# Audio_Input_Mic_In.net
KiCad netlist of a schematic drawn in Altium Designer
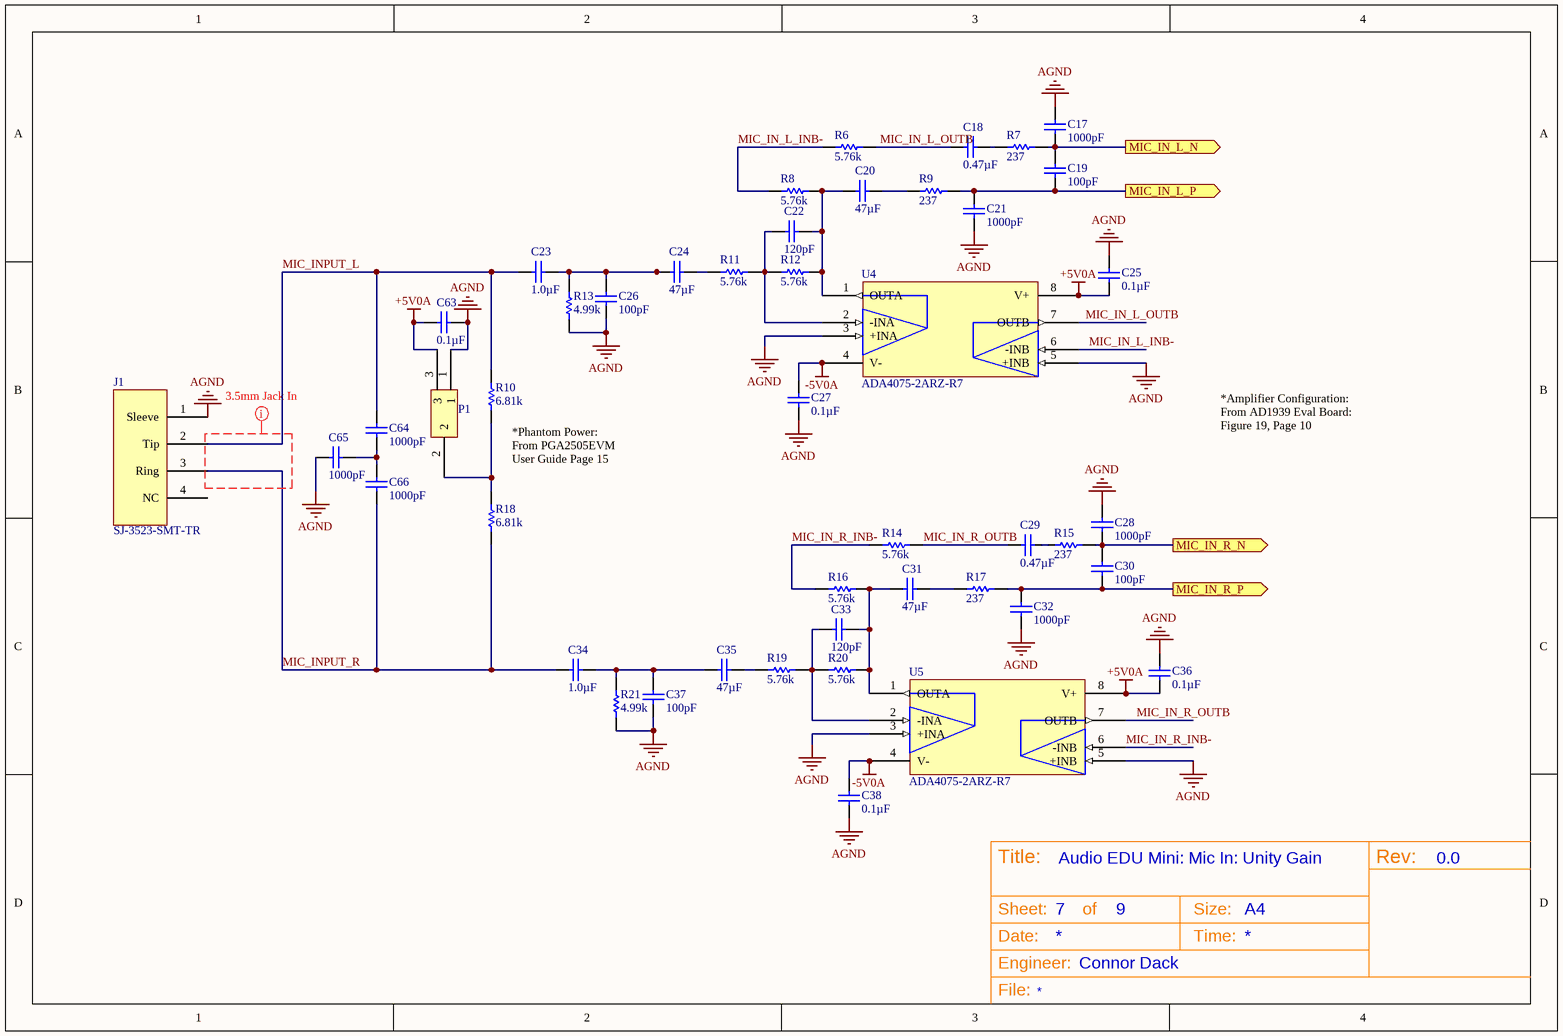
[diagram p0: Audio_Input_Mic_In.SchDoc]

(export (version "E")
  (design (tool "Eeschema 10.0.6"))
  (components
    (comp (ref "C17")
      (value "CL10B102KB8NNNC")
      (footprint "3-0603_L")
      (description "1000pF 50V Ceramic Capacitor X7R 0603 (1608 Metric) 0.063\" L x 0.031\" W (1.60mm x 0.80mm)")
      (fields
        (field (name "MANUFACTURER") "Samsung Electro-Mechanics America, Inc.")
        (field (name "TOLERANCE") "±10%")
        (field (name "CAPACITANCE") "1000pF")
      )
      (libsource (lib "Schematic_Components") (part "CL10B102KB8NNNC"))
    )
    (comp (ref "C18")
      (value "C1608X7R1H474K080AC")
      (footprint "3-0603_L")
      (description "CAP CER 0.47UF 50V 10% X7R 0603")
      (fields
        (field (name "MANUFACTURER") "TDK Corporation")
        (field (name "TOLERANCE") "±10%")
        (field (name "CAPACITANCE") "0.47µF")
      )
      (libsource (lib "Schematic_Components") (part "C1608X7R1H474K080AC"))
    )
    (comp (ref "C19")
      (value "C1608C0G2A101J")
      (footprint "3-0603_L")
      (description "CAP CER 100PF 100V 5% NP0 0603")
      (fields
        (field (name "MANUFACTURER") "TDK Corporation")
        (field (name "TOLERANCE") "±5%")
        (field (name "CAPACITANCE") "100pF")
      )
      (libsource (lib "Schematic_Components") (part "C1608C0G2A101J"))
    )
    (comp (ref "C20")
      (value "GRM32EC81C476KE15L")
      (footprint "C1210X25_L")
      (description "47µF ±10% 16V Ceramic Capacitor X6S 1210 (3225 Metric)")
      (fields
        (field (name "MANUFACTURER") "Murata Electronics North America")
        (field (name "TOLERANCE") "±10%")
        (field (name "CAPACITANCE") "47µF")
      )
      (libsource (lib "Schematic_Components") (part "GRM32EC81C476KE15L"))
    )
    (comp (ref "C21")
      (value "CL10B102KB8NNNC")
      (footprint "3-0603_L")
      (description "1000pF 50V Ceramic Capacitor X7R 0603 (1608 Metric) 0.063\" L x 0.031\" W (1.60mm x 0.80mm)")
      (fields
        (field (name "MANUFACTURER") "Samsung Electro-Mechanics America, Inc.")
        (field (name "TOLERANCE") "±10%")
        (field (name "CAPACITANCE") "1000pF")
      )
      (libsource (lib "Schematic_Components") (part "CL10B102KB8NNNC"))
    )
    (comp (ref "C22")
      (value "CL10C121JB8NCNC")
      (footprint "3-0603_L")
      (description "120pF 50V Ceramic Capacitor C0G, NP0 0603 (1608 Metric) 0.063\" L x 0.031\" W (1.60mm x 0.80mm)")
      (fields
        (field (name "MANUFACTURER") "Samsung Electro-Mechanics America, Inc.")
        (field (name "TOLERANCE") "±5%")
        (field (name "CAPACITANCE") "120pF")
      )
      (libsource (lib "Schematic_Components") (part "CL10C121JB8NCNC"))
    )
    (comp (ref "C23")
      (value "C1608X7R1C105K")
      (footprint "3-0603_L")
      (description "CAP CER 1UF 16V 10% X7R 0603")
      (fields
        (field (name "MANUFACTURER") "TDK Corporation")
        (field (name "TOLERANCE") "±10%")
        (field (name "CAPACITANCE") "1.0µF")
      )
      (libsource (lib "Schematic_Components") (part "C1608X7R1C105K"))
    )
    (comp (ref "C24")
      (value "GRM32EC81C476KE15L")
      (footprint "C1210X25_L")
      (description "47µF ±10% 16V Ceramic Capacitor X6S 1210 (3225 Metric)")
      (fields
        (field (name "MANUFACTURER") "Murata Electronics North America")
        (field (name "TOLERANCE") "±10%")
        (field (name "CAPACITANCE") "47µF")
      )
      (libsource (lib "Schematic_Components") (part "GRM32EC81C476KE15L"))
    )
    (comp (ref "C25")
      (value "C1608X7R1H104K")
      (footprint "3-0603_L")
      (description "CAP CER 0.1UF 50V 10% X7R 0603")
      (fields
        (field (name "MANUFACTURER") "TDK Corporation")
        (field (name "TOLERANCE") "±10%")
        (field (name "CAPACITANCE") "0.1µF")
      )
      (libsource (lib "Schematic_Components") (part "C1608X7R1H104K"))
    )
    (comp (ref "C26")
      (value "C1608C0G2A101J")
      (footprint "3-0603_L")
      (description "CAP CER 100PF 100V 5% NP0 0603")
      (fields
        (field (name "MANUFACTURER") "TDK Corporation")
        (field (name "TOLERANCE") "±5%")
        (field (name "CAPACITANCE") "100pF")
      )
      (libsource (lib "Schematic_Components") (part "C1608C0G2A101J"))
    )
    (comp (ref "C27")
      (value "C1608X7R1H104K")
      (footprint "3-0603_L")
      (description "CAP CER 0.1UF 50V 10% X7R 0603")
      (fields
        (field (name "MANUFACTURER") "TDK Corporation")
        (field (name "TOLERANCE") "±10%")
        (field (name "CAPACITANCE") "0.1µF")
      )
      (libsource (lib "Schematic_Components") (part "C1608X7R1H104K"))
    )
    (comp (ref "C28")
      (value "CL10B102KB8NNNC")
      (footprint "3-0603_L")
      (description "1000pF 50V Ceramic Capacitor X7R 0603 (1608 Metric) 0.063\" L x 0.031\" W (1.60mm x 0.80mm)")
      (fields
        (field (name "MANUFACTURER") "Samsung Electro-Mechanics America, Inc.")
        (field (name "TOLERANCE") "±10%")
        (field (name "CAPACITANCE") "1000pF")
      )
      (libsource (lib "Schematic_Components") (part "CL10B102KB8NNNC"))
    )
    (comp (ref "C29")
      (value "C1608X7R1H474K080AC")
      (footprint "3-0603_L")
      (description "CAP CER 0.47UF 50V 10% X7R 0603")
      (fields
        (field (name "MANUFACTURER") "TDK Corporation")
        (field (name "TOLERANCE") "±10%")
        (field (name "CAPACITANCE") "0.47µF")
      )
      (libsource (lib "Schematic_Components") (part "C1608X7R1H474K080AC"))
    )
    (comp (ref "C30")
      (value "C1608C0G2A101J")
      (footprint "3-0603_L")
      (description "CAP CER 100PF 100V 5% NP0 0603")
      (fields
        (field (name "MANUFACTURER") "TDK Corporation")
        (field (name "TOLERANCE") "±5%")
        (field (name "CAPACITANCE") "100pF")
      )
      (libsource (lib "Schematic_Components") (part "C1608C0G2A101J"))
    )
    (comp (ref "C31")
      (value "GRM32EC81C476KE15L")
      (footprint "C1210X25_L")
      (description "47µF ±10% 16V Ceramic Capacitor X6S 1210 (3225 Metric)")
      (fields
        (field (name "MANUFACTURER") "Murata Electronics North America")
        (field (name "TOLERANCE") "±10%")
        (field (name "CAPACITANCE") "47µF")
      )
      (libsource (lib "Schematic_Components") (part "GRM32EC81C476KE15L"))
    )
    (comp (ref "C32")
      (value "CL10B102KB8NNNC")
      (footprint "3-0603_L")
      (description "1000pF 50V Ceramic Capacitor X7R 0603 (1608 Metric) 0.063\" L x 0.031\" W (1.60mm x 0.80mm)")
      (fields
        (field (name "MANUFACTURER") "Samsung Electro-Mechanics America, Inc.")
        (field (name "TOLERANCE") "±10%")
        (field (name "CAPACITANCE") "1000pF")
      )
      (libsource (lib "Schematic_Components") (part "CL10B102KB8NNNC"))
    )
    (comp (ref "C33")
      (value "CL10C121JB8NCNC")
      (footprint "3-0603_L")
      (description "120pF 50V Ceramic Capacitor C0G, NP0 0603 (1608 Metric) 0.063\" L x 0.031\" W (1.60mm x 0.80mm)")
      (fields
        (field (name "MANUFACTURER") "Samsung Electro-Mechanics America, Inc.")
        (field (name "TOLERANCE") "±5%")
        (field (name "CAPACITANCE") "120pF")
      )
      (libsource (lib "Schematic_Components") (part "CL10C121JB8NCNC"))
    )
    (comp (ref "C34")
      (value "C1608X7R1C105K")
      (footprint "3-0603_L")
      (description "CAP CER 1UF 16V 10% X7R 0603")
      (fields
        (field (name "MANUFACTURER") "TDK Corporation")
        (field (name "TOLERANCE") "±10%")
        (field (name "CAPACITANCE") "1.0µF")
      )
      (libsource (lib "Schematic_Components") (part "C1608X7R1C105K"))
    )
    (comp (ref "C35")
      (value "GRM32EC81C476KE15L")
      (footprint "C1210X25_L")
      (description "47µF ±10% 16V Ceramic Capacitor X6S 1210 (3225 Metric)")
      (fields
        (field (name "MANUFACTURER") "Murata Electronics North America")
        (field (name "TOLERANCE") "±10%")
        (field (name "CAPACITANCE") "47µF")
      )
      (libsource (lib "Schematic_Components") (part "GRM32EC81C476KE15L"))
    )
    (comp (ref "C36")
      (value "C1608X7R1H104K")
      (footprint "3-0603_L")
      (description "CAP CER 0.1UF 50V 10% X7R 0603")
      (fields
        (field (name "MANUFACTURER") "TDK Corporation")
        (field (name "TOLERANCE") "±10%")
        (field (name "CAPACITANCE") "0.1µF")
      )
      (libsource (lib "Schematic_Components") (part "C1608X7R1H104K"))
    )
    (comp (ref "C37")
      (value "C1608C0G2A101J")
      (footprint "3-0603_L")
      (description "CAP CER 100PF 100V 5% NP0 0603")
      (fields
        (field (name "MANUFACTURER") "TDK Corporation")
        (field (name "TOLERANCE") "±5%")
        (field (name "CAPACITANCE") "100pF")
      )
      (libsource (lib "Schematic_Components") (part "C1608C0G2A101J"))
    )
    (comp (ref "C38")
      (value "C1608X7R1H104K")
      (footprint "3-0603_L")
      (description "CAP CER 0.1UF 50V 10% X7R 0603")
      (fields
        (field (name "MANUFACTURER") "TDK Corporation")
        (field (name "TOLERANCE") "±10%")
        (field (name "CAPACITANCE") "0.1µF")
      )
      (libsource (lib "Schematic_Components") (part "C1608X7R1H104K"))
    )
    (comp (ref "C63")
      (value "C1608X7R1H104K")
      (footprint "3-0603_L")
      (description "CAP CER 0.1UF 50V 10% X7R 0603")
      (fields
        (field (name "MANUFACTURER") "TDK Corporation")
        (field (name "TOLERANCE") "±10%")
        (field (name "CAPACITANCE") "0.1µF")
      )
      (libsource (lib "Schematic_Components") (part "C1608X7R1H104K"))
    )
    (comp (ref "C64")
      (value "C1608C0G1H102J")
      (footprint "3-0603_L")
      (description "CAP CER 1000PF 50V 5% NP0 0603")
      (fields
        (field (name "MANUFACTURER") "TDK Corporation")
        (field (name "TOLERANCE") "±5%")
        (field (name "CAPACITANCE") "1000pF")
      )
      (libsource (lib "Schematic_Components") (part "C1608C0G1H102J"))
    )
    (comp (ref "C65")
      (value "C1608C0G1H102J")
      (footprint "3-0603_L")
      (description "CAP CER 1000PF 50V 5% NP0 0603")
      (fields
        (field (name "MANUFACTURER") "TDK Corporation")
        (field (name "TOLERANCE") "±5%")
        (field (name "CAPACITANCE") "1000pF")
      )
      (libsource (lib "Schematic_Components") (part "C1608C0G1H102J"))
    )
    (comp (ref "C66")
      (value "C1608C0G1H102J")
      (footprint "3-0603_L")
      (description "CAP CER 1000PF 50V 5% NP0 0603")
      (fields
        (field (name "MANUFACTURER") "TDK Corporation")
        (field (name "TOLERANCE") "±5%")
        (field (name "CAPACITANCE") "1000pF")
      )
      (libsource (lib "Schematic_Components") (part "C1608C0G1H102J"))
    )
    (comp (ref "J1")
      (value "SJ-3523-SMT-TR")
      (footprint "SJ-3523-SMT-TR")
      (description "3.50mm (0.141\", 1/8\", Mini Plug) - Headphone Phone Jack Stereo Connector Solder")
      (fields
        (field (name "MANUFACTURER") "CUI Inc.")
        (field (name "MANUFACTURER PART NUMBER") "SJ-3523-SMT-TR")
        (field (name "PUBLISHER") "Altium Limited")
      )
      (libsource (lib "NIH_DE0_Nano_Daughter_Card_Library") (part "SJ-3523-SMT-TR"))
    )
    (comp (ref "P1")
      (value "3PIN_Connector")
      (footprint "3Pin_Header")
      (description "3 Pin Through Hole Connector with 0.1\" Spacing")
      (fields
        (field (name "MANUFACTURER") "Samtec")
        (field (name "MANUFACTURER PART NUMBER") "TSW-103-07-G-S")
        (field (name "PUBLISHER") "Altium Limited")
      )
      (libsource (lib "Schematic_Components_CD") (part "CONN_TH_3PIN_0D1"))
    )
    (comp (ref "R6")
      (value "ERJ-3EKF5761V")
      (footprint "3-0603_R_L")
      (description "RES SMD 5.76K OHM 1% 1/10W 0603")
      (fields
        (field (name "MANUFACTURER") "Panasonic Electronic Components")
        (field (name "TOLERANCE") "±1%")
        (field (name "RESISTANCE (OHMS)") "5.76k")
      )
      (libsource (lib "Schematic_Components") (part "ERJ-3EKF5761V"))
    )
    (comp (ref "R7")
      (value "ERJ-3EKF2370V")
      (footprint "3-0603_R_L")
      (description "RES SMD 237 OHM 1% 1/10W 0603")
      (fields
        (field (name "MANUFACTURER") "Panasonic Electronic Components")
        (field (name "TOLERANCE") "±1%")
        (field (name "RESISTANCE (OHMS)") "237")
      )
      (libsource (lib "Schematic_Components") (part "ERJ-3EKF2370V"))
    )
    (comp (ref "R8")
      (value "ERJ-3EKF5761V")
      (footprint "3-0603_R_L")
      (description "RES SMD 5.76K OHM 1% 1/10W 0603")
      (fields
        (field (name "MANUFACTURER") "Panasonic Electronic Components")
        (field (name "TOLERANCE") "±1%")
        (field (name "RESISTANCE (OHMS)") "5.76k")
      )
      (libsource (lib "Schematic_Components") (part "ERJ-3EKF5761V"))
    )
    (comp (ref "R9")
      (value "ERJ-3EKF2370V")
      (footprint "3-0603_R_L")
      (description "RES SMD 237 OHM 1% 1/10W 0603")
      (fields
        (field (name "MANUFACTURER") "Panasonic Electronic Components")
        (field (name "TOLERANCE") "±1%")
        (field (name "RESISTANCE (OHMS)") "237")
      )
      (libsource (lib "Schematic_Components") (part "ERJ-3EKF2370V"))
    )
    (comp (ref "R10")
      (value "ERJ-3EKF6811V")
      (footprint "3-0603_R_L")
      (description "RES SMD 6.81K OHM 1% 1/10W 0603")
      (fields
        (field (name "MANUFACTURER") "Panasonic ECG")
        (field (name "TOLERANCE") "1%")
        (field (name "RESISTANCE") "6.81k")
      )
      (libsource (lib "Schematic_Components_CD") (part "ERJ-3EKF6811V"))
    )
    (comp (ref "R11")
      (value "ERJ-3EKF5761V")
      (footprint "3-0603_R_L")
      (description "RES SMD 5.76K OHM 1% 1/10W 0603")
      (fields
        (field (name "MANUFACTURER") "Panasonic Electronic Components")
        (field (name "TOLERANCE") "±1%")
        (field (name "RESISTANCE (OHMS)") "5.76k")
      )
      (libsource (lib "Schematic_Components") (part "ERJ-3EKF5761V"))
    )
    (comp (ref "R12")
      (value "ERJ-3EKF5761V")
      (footprint "3-0603_R_L")
      (description "RES SMD 5.76K OHM 1% 1/10W 0603")
      (fields
        (field (name "MANUFACTURER") "Panasonic Electronic Components")
        (field (name "TOLERANCE") "±1%")
        (field (name "RESISTANCE (OHMS)") "5.76k")
      )
      (libsource (lib "Schematic_Components") (part "ERJ-3EKF5761V"))
    )
    (comp (ref "R13")
      (value "ERJ-3EKF4991V")
      (footprint "3-0603_R_L")
      (description "RES SMD 4.99K OHM 1% 1/10W 0603")
      (fields
        (field (name "MANUFACTURER") "Panasonic Electronic Components")
        (field (name "TOLERANCE") "±1%")
        (field (name "RESISTANCE (OHMS)") "4.99k")
      )
      (libsource (lib "Schematic_Components") (part "ERJ-3EKF4991V"))
    )
    (comp (ref "R14")
      (value "ERJ-3EKF5761V")
      (footprint "3-0603_R_L")
      (description "RES SMD 5.76K OHM 1% 1/10W 0603")
      (fields
        (field (name "MANUFACTURER") "Panasonic Electronic Components")
        (field (name "TOLERANCE") "±1%")
        (field (name "RESISTANCE (OHMS)") "5.76k")
      )
      (libsource (lib "Schematic_Components") (part "ERJ-3EKF5761V"))
    )
    (comp (ref "R15")
      (value "ERJ-3EKF2370V")
      (footprint "3-0603_R_L")
      (description "RES SMD 237 OHM 1% 1/10W 0603")
      (fields
        (field (name "MANUFACTURER") "Panasonic Electronic Components")
        (field (name "TOLERANCE") "±1%")
        (field (name "RESISTANCE (OHMS)") "237")
      )
      (libsource (lib "Schematic_Components") (part "ERJ-3EKF2370V"))
    )
    (comp (ref "R16")
      (value "ERJ-3EKF5761V")
      (footprint "3-0603_R_L")
      (description "RES SMD 5.76K OHM 1% 1/10W 0603")
      (fields
        (field (name "MANUFACTURER") "Panasonic Electronic Components")
        (field (name "TOLERANCE") "±1%")
        (field (name "RESISTANCE (OHMS)") "5.76k")
      )
      (libsource (lib "Schematic_Components") (part "ERJ-3EKF5761V"))
    )
    (comp (ref "R17")
      (value "ERJ-3EKF2370V")
      (footprint "3-0603_R_L")
      (description "RES SMD 237 OHM 1% 1/10W 0603")
      (fields
        (field (name "MANUFACTURER") "Panasonic Electronic Components")
        (field (name "TOLERANCE") "±1%")
        (field (name "RESISTANCE (OHMS)") "237")
      )
      (libsource (lib "Schematic_Components") (part "ERJ-3EKF2370V"))
    )
    (comp (ref "R18")
      (value "ERJ-3EKF6811V")
      (footprint "3-0603_R_L")
      (description "RES SMD 6.81K OHM 1% 1/10W 0603")
      (fields
        (field (name "MANUFACTURER") "Panasonic ECG")
        (field (name "TOLERANCE") "1%")
        (field (name "RESISTANCE") "6.81k")
      )
      (libsource (lib "Schematic_Components_CD") (part "ERJ-3EKF6811V"))
    )
    (comp (ref "R19")
      (value "ERJ-3EKF5761V")
      (footprint "3-0603_R_L")
      (description "RES SMD 5.76K OHM 1% 1/10W 0603")
      (fields
        (field (name "MANUFACTURER") "Panasonic Electronic Components")
        (field (name "TOLERANCE") "±1%")
        (field (name "RESISTANCE (OHMS)") "5.76k")
      )
      (libsource (lib "Schematic_Components") (part "ERJ-3EKF5761V"))
    )
    (comp (ref "R20")
      (value "ERJ-3EKF5761V")
      (footprint "3-0603_R_L")
      (description "RES SMD 5.76K OHM 1% 1/10W 0603")
      (fields
        (field (name "MANUFACTURER") "Panasonic Electronic Components")
        (field (name "TOLERANCE") "±1%")
        (field (name "RESISTANCE (OHMS)") "5.76k")
      )
      (libsource (lib "Schematic_Components") (part "ERJ-3EKF5761V"))
    )
    (comp (ref "R21")
      (value "ERJ-3EKF4991V")
      (footprint "3-0603_R_L")
      (description "RES SMD 4.99K OHM 1% 1/10W 0603")
      (fields
        (field (name "MANUFACTURER") "Panasonic Electronic Components")
        (field (name "TOLERANCE") "±1%")
        (field (name "RESISTANCE (OHMS)") "4.99k")
      )
      (libsource (lib "Schematic_Components") (part "ERJ-3EKF4991V"))
    )
    (comp (ref "U4")
      (value "ADA4075-2ARZ-R7")
      (footprint "SOIC127P600X175-8L")
      (description "IC OPAMP GP 6.5MHZ 8SOIC")
      (fields
        (field (name "MANUFACTURER") "Analog Devices Inc.")
        (field (name "MANUFACTURER PART NUMBER") "ADA4075-2ARZ-R7")
      )
      (libsource (lib "NIH_DE0_Nano_Daughter_Card_Library") (part "ADA4075-2ARZ-R7"))
    )
    (comp (ref "U5")
      (value "ADA4075-2ARZ-R7")
      (footprint "SOIC127P600X175-8L")
      (description "IC OPAMP GP 6.5MHZ 8SOIC")
      (fields
        (field (name "MANUFACTURER") "Analog Devices Inc.")
        (field (name "MANUFACTURER PART NUMBER") "ADA4075-2ARZ-R7")
      )
      (libsource (lib "NIH_DE0_Nano_Daughter_Card_Library") (part "ADA4075-2ARZ-R7"))
    )
  )
  (nets
    (net (code "1") (name "+5V0A") (class "Default")
      (node (ref "C25") (pin "1") (pinfunction "1_1") (pintype "passive"))
      (node (ref "C36") (pin "1") (pinfunction "1_1") (pintype "passive"))
      (node (ref "C63") (pin "2") (pinfunction "2_2") (pintype "passive"))
      (node (ref "P1") (pin "3") (pinfunction "3_3") (pintype "passive"))
      (node (ref "U4") (pin "8") (pinfunction "V+_8") (pintype "passive"))
      (node (ref "U5") (pin "8") (pinfunction "V+_8") (pintype "passive"))
    )
    (net (code "2") (name "-5V0A") (class "Default")
      (node (ref "C27") (pin "1") (pinfunction "1_1") (pintype "passive"))
      (node (ref "C38") (pin "1") (pinfunction "1_1") (pintype "passive"))
      (node (ref "U4") (pin "4") (pinfunction "V-_4") (pintype "passive"))
      (node (ref "U5") (pin "4") (pinfunction "V-_4") (pintype "passive"))
    )
    (net (code "3") (name "/MIC_INPUT_L") (class "Default")
      (node (ref "C23") (pin "1") (pinfunction "1_1") (pintype "passive"))
      (node (ref "C64") (pin "2") (pinfunction "2_2") (pintype "passive"))
      (node (ref "J1") (pin "2") (pinfunction "Tip_2") (pintype "passive"))
      (node (ref "R10") (pin "2") (pinfunction "2_2") (pintype "passive"))
    )
    (net (code "4") (name "/MIC_INPUT_R") (class "Default")
      (node (ref "C34") (pin "1") (pinfunction "1_1") (pintype "passive"))
      (node (ref "C66") (pin "1") (pinfunction "1_1") (pintype "passive"))
      (node (ref "J1") (pin "3") (pinfunction "Ring_3") (pintype "passive"))
      (node (ref "R18") (pin "1") (pinfunction "1_1") (pintype "passive"))
    )
    (net (code "5") (name "/MIC_IN_L_INB-") (class "Default")
      (node (ref "R6") (pin "1") (pinfunction "1_1") (pintype "passive"))
      (node (ref "R8") (pin "1") (pinfunction "1_1") (pintype "passive"))
      (node (ref "U4") (pin "6") (pinfunction "-INB_6") (pintype "input"))
    )
    (net (code "6") (name "/MIC_IN_L_N") (class "Default")
      (node (ref "C17") (pin "2") (pinfunction "2_2") (pintype "passive"))
      (node (ref "C19") (pin "2") (pinfunction "2_2") (pintype "passive"))
      (node (ref "R7") (pin "2") (pinfunction "2_2") (pintype "passive"))
    )
    (net (code "7") (name "/MIC_IN_L_OUTB") (class "Default")
      (node (ref "C18") (pin "1") (pinfunction "1_1") (pintype "passive"))
      (node (ref "R6") (pin "2") (pinfunction "2_2") (pintype "passive"))
      (node (ref "U4") (pin "7") (pinfunction "OUTB_7") (pintype "output"))
    )
    (net (code "8") (name "/MIC_IN_L_P") (class "Default")
      (node (ref "C19") (pin "1") (pinfunction "1_1") (pintype "passive"))
      (node (ref "C21") (pin "2") (pinfunction "2_2") (pintype "passive"))
      (node (ref "R9") (pin "2") (pinfunction "2_2") (pintype "passive"))
    )
    (net (code "9") (name "/MIC_IN_R_INB-") (class "Default")
      (node (ref "R14") (pin "1") (pinfunction "1_1") (pintype "passive"))
      (node (ref "R16") (pin "1") (pinfunction "1_1") (pintype "passive"))
      (node (ref "U5") (pin "6") (pinfunction "-INB_6") (pintype "input"))
    )
    (net (code "10") (name "/MIC_IN_R_N") (class "Default")
      (node (ref "C28") (pin "2") (pinfunction "2_2") (pintype "passive"))
      (node (ref "C30") (pin "2") (pinfunction "2_2") (pintype "passive"))
      (node (ref "R15") (pin "2") (pinfunction "2_2") (pintype "passive"))
    )
    (net (code "11") (name "/MIC_IN_R_OUTB") (class "Default")
      (node (ref "C29") (pin "1") (pinfunction "1_1") (pintype "passive"))
      (node (ref "R14") (pin "2") (pinfunction "2_2") (pintype "passive"))
      (node (ref "U5") (pin "7") (pinfunction "OUTB_7") (pintype "output"))
    )
    (net (code "12") (name "/MIC_IN_R_P") (class "Default")
      (node (ref "C30") (pin "1") (pinfunction "1_1") (pintype "passive"))
      (node (ref "C32") (pin "2") (pinfunction "2_2") (pintype "passive"))
      (node (ref "R17") (pin "2") (pinfunction "2_2") (pintype "passive"))
    )
    (net (code "13") (name "AGND") (class "Default")
      (node (ref "C17") (pin "1") (pinfunction "1_1") (pintype "passive"))
      (node (ref "C21") (pin "1") (pinfunction "1_1") (pintype "passive"))
      (node (ref "C25") (pin "2") (pinfunction "2_2") (pintype "passive"))
      (node (ref "C26") (pin "2") (pinfunction "2_2") (pintype "passive"))
      (node (ref "C27") (pin "2") (pinfunction "2_2") (pintype "passive"))
      (node (ref "C28") (pin "1") (pinfunction "1_1") (pintype "passive"))
      (node (ref "C32") (pin "1") (pinfunction "1_1") (pintype "passive"))
      (node (ref "C36") (pin "2") (pinfunction "2_2") (pintype "passive"))
      (node (ref "C37") (pin "2") (pinfunction "2_2") (pintype "passive"))
      (node (ref "C38") (pin "2") (pinfunction "2_2") (pintype "passive"))
      (node (ref "C63") (pin "1") (pinfunction "1_1") (pintype "passive"))
      (node (ref "C65") (pin "2") (pinfunction "2_2") (pintype "passive"))
      (node (ref "J1") (pin "1") (pinfunction "Sleeve_1") (pintype "passive"))
      (node (ref "P1") (pin "1") (pinfunction "1_1") (pintype "passive"))
      (node (ref "R13") (pin "1") (pinfunction "1_1") (pintype "passive"))
      (node (ref "R21") (pin "1") (pinfunction "1_1") (pintype "passive"))
      (node (ref "U4") (pin "3") (pinfunction "+INA_3") (pintype "input"))
      (node (ref "U4") (pin "5") (pinfunction "+INB_5") (pintype "input"))
      (node (ref "U5") (pin "3") (pinfunction "+INA_3") (pintype "input"))
      (node (ref "U5") (pin "5") (pinfunction "+INB_5") (pintype "input"))
    )
    (net (code "14") (name "Net-(C18-Pad2)") (class "Default")
      (node (ref "C18") (pin "2") (pinfunction "2_2") (pintype "passive"))
      (node (ref "R7") (pin "1") (pinfunction "1_1") (pintype "passive"))
    )
    (net (code "15") (name "Net-(C20-Pad2)") (class "Default")
      (node (ref "C20") (pin "2") (pinfunction "2_2") (pintype "passive"))
      (node (ref "R9") (pin "1") (pinfunction "1_1") (pintype "passive"))
    )
    (net (code "16") (name "Net-(C23-Pad2)") (class "Default")
      (node (ref "C23") (pin "2") (pinfunction "2_2") (pintype "passive"))
      (node (ref "C24") (pin "1") (pinfunction "1_1") (pintype "passive"))
      (node (ref "C26") (pin "1") (pinfunction "1_1") (pintype "passive"))
      (node (ref "R13") (pin "2") (pinfunction "2_2") (pintype "passive"))
    )
    (net (code "17") (name "Net-(C24-Pad2)") (class "Default")
      (node (ref "C24") (pin "2") (pinfunction "2_2") (pintype "passive"))
      (node (ref "R11") (pin "1") (pinfunction "1_1") (pintype "passive"))
    )
    (net (code "18") (name "Net-(C29-Pad2)") (class "Default")
      (node (ref "C29") (pin "2") (pinfunction "2_2") (pintype "passive"))
      (node (ref "R15") (pin "1") (pinfunction "1_1") (pintype "passive"))
    )
    (net (code "19") (name "Net-(C31-Pad2)") (class "Default")
      (node (ref "C31") (pin "2") (pinfunction "2_2") (pintype "passive"))
      (node (ref "R17") (pin "1") (pinfunction "1_1") (pintype "passive"))
    )
    (net (code "20") (name "Net-(C34-Pad2)") (class "Default")
      (node (ref "C34") (pin "2") (pinfunction "2_2") (pintype "passive"))
      (node (ref "C35") (pin "1") (pinfunction "1_1") (pintype "passive"))
      (node (ref "C37") (pin "1") (pinfunction "1_1") (pintype "passive"))
      (node (ref "R21") (pin "2") (pinfunction "2_2") (pintype "passive"))
    )
    (net (code "21") (name "Net-(C35-Pad2)") (class "Default")
      (node (ref "C35") (pin "2") (pinfunction "2_2") (pintype "passive"))
      (node (ref "R19") (pin "1") (pinfunction "1_1") (pintype "passive"))
    )
    (net (code "22") (name "Net-(C64-Pad1)") (class "Default")
      (node (ref "C64") (pin "1") (pinfunction "1_1") (pintype "passive"))
      (node (ref "C65") (pin "1") (pinfunction "1_1") (pintype "passive"))
      (node (ref "C66") (pin "2") (pinfunction "2_2") (pintype "passive"))
    )
    (net (code "23") (name "Net-(P1-Pad2)") (class "Default")
      (node (ref "P1") (pin "2") (pinfunction "2_2") (pintype "passive"))
      (node (ref "R10") (pin "1") (pinfunction "1_1") (pintype "passive"))
      (node (ref "R18") (pin "2") (pinfunction "2_2") (pintype "passive"))
    )
    (net (code "24") (name "Net-(U4--INA)") (class "Default")
      (node (ref "C22") (pin "1") (pinfunction "1_1") (pintype "passive"))
      (node (ref "R11") (pin "2") (pinfunction "2_2") (pintype "passive"))
      (node (ref "R12") (pin "1") (pinfunction "1_1") (pintype "passive"))
      (node (ref "U4") (pin "2") (pinfunction "-INA_2") (pintype "input"))
    )
    (net (code "25") (name "Net-(U4-OUTA)") (class "Default")
      (node (ref "C20") (pin "1") (pinfunction "1_1") (pintype "passive"))
      (node (ref "C22") (pin "2") (pinfunction "2_2") (pintype "passive"))
      (node (ref "R12") (pin "2") (pinfunction "2_2") (pintype "passive"))
      (node (ref "R8") (pin "2") (pinfunction "2_2") (pintype "passive"))
      (node (ref "U4") (pin "1") (pinfunction "OUTA_1") (pintype "output"))
    )
    (net (code "26") (name "Net-(U5--INA)") (class "Default")
      (node (ref "C33") (pin "1") (pinfunction "1_1") (pintype "passive"))
      (node (ref "R19") (pin "2") (pinfunction "2_2") (pintype "passive"))
      (node (ref "R20") (pin "1") (pinfunction "1_1") (pintype "passive"))
      (node (ref "U5") (pin "2") (pinfunction "-INA_2") (pintype "input"))
    )
    (net (code "27") (name "Net-(U5-OUTA)") (class "Default")
      (node (ref "C31") (pin "1") (pinfunction "1_1") (pintype "passive"))
      (node (ref "C33") (pin "2") (pinfunction "2_2") (pintype "passive"))
      (node (ref "R16") (pin "2") (pinfunction "2_2") (pintype "passive"))
      (node (ref "R20") (pin "2") (pinfunction "2_2") (pintype "passive"))
      (node (ref "U5") (pin "1") (pinfunction "OUTA_1") (pintype "output"))
    )
    (net (code "28") (name "unconnected-(J1-NC-Pad4)") (class "Default")
      (node (ref "J1") (pin "4") (pinfunction "NC_4") (pintype "passive"))
    )
  )
)
